# Main-board.net
KiCad netlist of a schematic drawn in EAGLE
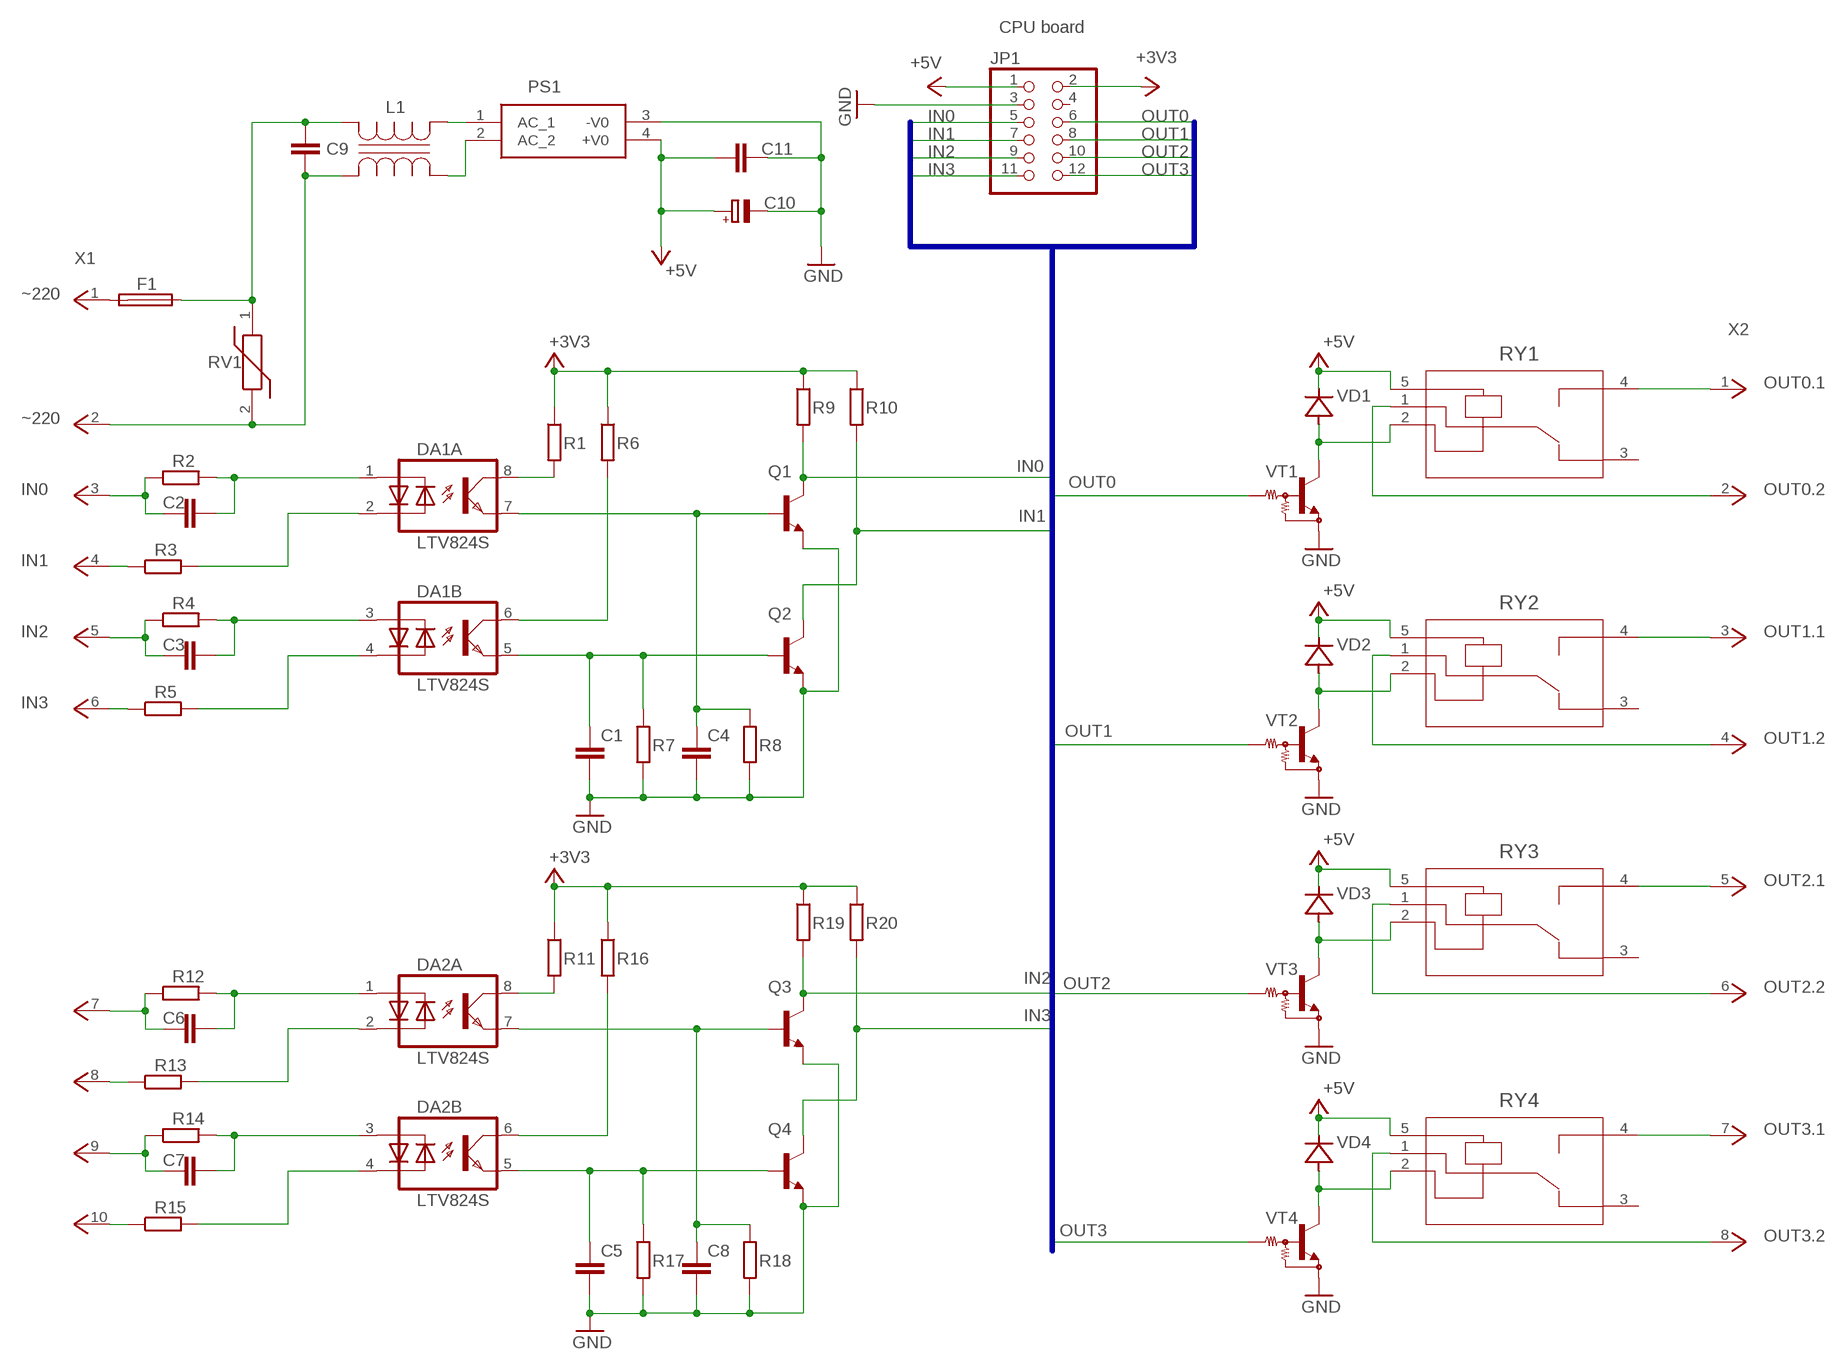
[diagram p0: schematic, sheet 1]

(export (version "E")
  (design (tool "Eeschema 10.0.6"))
  (components
    (comp (ref "C1")
      (value "0,1u")
      (footprint "eagle-import:C0603")
      (fields (field (name "VOLTAGE") "50V"))
      (libsource (lib "eagle-import") (part "C-EUC0603"))
    )
    (comp (ref "C2")
      (value "33n")
      (footprint "eagle-import:C1812")
      (fields (field (name "VOLTAGE") "500V"))
      (libsource (lib "eagle-import") (part "C-EUC1812"))
    )
    (comp (ref "C3")
      (value "33n")
      (footprint "eagle-import:C1812")
      (fields (field (name "VOLTAGE") "500V"))
      (libsource (lib "eagle-import") (part "C-EUC1812"))
    )
    (comp (ref "C4")
      (value "0,1u")
      (footprint "eagle-import:C0603")
      (fields (field (name "VOLTAGE") "50V"))
      (libsource (lib "eagle-import") (part "C-EUC0603"))
    )
    (comp (ref "C5")
      (value "0,1u")
      (footprint "eagle-import:C0603")
      (fields (field (name "VOLTAGE") "50V"))
      (libsource (lib "eagle-import") (part "C-EUC0603"))
    )
    (comp (ref "C6")
      (value "33n")
      (footprint "eagle-import:C1812")
      (fields (field (name "VOLTAGE") "500V"))
      (libsource (lib "eagle-import") (part "C-EUC1812"))
    )
    (comp (ref "C7")
      (value "33n")
      (footprint "eagle-import:C1812")
      (fields (field (name "VOLTAGE") "500V"))
      (libsource (lib "eagle-import") (part "C-EUC1812"))
    )
    (comp (ref "C8")
      (value "0,1u")
      (footprint "eagle-import:C0603")
      (fields (field (name "VOLTAGE") "50V"))
      (libsource (lib "eagle-import") (part "C-EUC0603"))
    )
    (comp (ref "C9")
      (value "R46KI310000M1K")
      (footprint "eagle-import:CAP_R46KI310000M1K")
      (fields (field (name "COPYRIGHT") "Copyright (C) 2018 Accelerated Designs. All rights reserved"))
      (libsource (lib "eagle-import") (part "R46KI310000M1K"))
    )
    (comp (ref "C10")
      (value "220uF")
      (footprint "eagle-import:D_7343-31W")
      (fields (field (name "TOLERANCE") "+/-10%") (field (name "VOLTAGE") "10V"))
      (libsource (lib "eagle-import") (part "CPOL-EUD/7343-31W"))
    )
    (comp (ref "C11")
      (value "0,1u")
      (footprint "eagle-import:C0603")
      (fields (field (name "VOLTAGE") "50V"))
      (libsource (lib "eagle-import") (part "C-EUC0603"))
    )
    (comp (ref "DA1")
      (value "LTV824S")
      (footprint "eagle-import:DIL8-SMD")
      (libsource (lib "eagle-import") (part "LTV824S"))
    )
    (comp (ref "DA2")
      (value "LTV824S")
      (footprint "eagle-import:DIL8-SMD")
      (libsource (lib "eagle-import") (part "LTV824S"))
    )
    (comp (ref "F1")
      (value "0,5A")
      (footprint "eagle-import:TR5")
      (libsource (lib "eagle-import") (part "TR5"))
    )
    (comp (ref "JP1")
      (value "NOT INSTALLED")
      (footprint "eagle-import:2X06")
      (libsource (lib "eagle-import") (part "PINHD-2X6"))
    )
    (comp (ref "L1")
      (value "DLW5BSN152SQ2L")
      (footprint "eagle-import:IND_DLW5BS_2020")
      (libsource (lib "eagle-import") (part "DLW5BSN152SQ2L"))
    )
    (comp (ref "PS1")
      (value "HLK-10M05")
      (footprint "eagle-import:HLK10M05")
      (libsource (lib "eagle-import") (part "HLK-10M05"))
    )
    (comp (ref "Q1")
      (value "BC847ALT1SMD")
      (footprint "eagle-import:SOT23")
      (libsource (lib "eagle-import") (part "BC847SMDALT1"))
    )
    (comp (ref "Q2")
      (value "BC847ALT1SMD")
      (footprint "eagle-import:SOT23")
      (libsource (lib "eagle-import") (part "BC847SMDALT1"))
    )
    (comp (ref "Q3")
      (value "BC847ALT1SMD")
      (footprint "eagle-import:SOT23")
      (libsource (lib "eagle-import") (part "BC847SMDALT1"))
    )
    (comp (ref "Q4")
      (value "BC847ALT1SMD")
      (footprint "eagle-import:SOT23")
      (libsource (lib "eagle-import") (part "BC847SMDALT1"))
    )
    (comp (ref "R1")
      (value "2,2k")
      (footprint "eagle-import:R0603")
      (fields (field (name "TOLERANCE") "1%"))
      (libsource (lib "eagle-import") (part "R-EU_R0603"))
    )
    (comp (ref "R2")
      (value "330k")
      (footprint "eagle-import:R2512")
      (fields (field (name "TOLERANCE") "5%"))
      (libsource (lib "eagle-import") (part "R-EU_R2512"))
    )
    (comp (ref "R3")
      (value "51")
      (footprint "eagle-import:R2512")
      (fields (field (name "TOLERANCE") "5%"))
      (libsource (lib "eagle-import") (part "R-EU_R2512"))
    )
    (comp (ref "R4")
      (value "330 k")
      (footprint "eagle-import:R2512")
      (fields (field (name "TOLERANCE") "5%"))
      (libsource (lib "eagle-import") (part "R-EU_R2512"))
    )
    (comp (ref "R5")
      (value "51")
      (footprint "eagle-import:R2512")
      (fields (field (name "TOLERANCE") "5%"))
      (libsource (lib "eagle-import") (part "R-EU_R2512"))
    )
    (comp (ref "R6")
      (value "2,2k")
      (footprint "eagle-import:R0603")
      (fields (field (name "TOLERANCE") "1%"))
      (libsource (lib "eagle-import") (part "R-EU_R0603"))
    )
    (comp (ref "R7")
      (value "33k")
      (footprint "eagle-import:R0603")
      (fields (field (name "TOLERANCE") "1%"))
      (libsource (lib "eagle-import") (part "R-EU_R0603"))
    )
    (comp (ref "R8")
      (value "33k")
      (footprint "eagle-import:R0603")
      (fields (field (name "TOLERANCE") "1%"))
      (libsource (lib "eagle-import") (part "R-EU_R0603"))
    )
    (comp (ref "R9")
      (value "10k")
      (footprint "eagle-import:R0603")
      (fields (field (name "TOLERANCE") "1%"))
      (libsource (lib "eagle-import") (part "R-EU_R0603"))
    )
    (comp (ref "R10")
      (value "10k")
      (footprint "eagle-import:R0603")
      (fields (field (name "TOLERANCE") "1%"))
      (libsource (lib "eagle-import") (part "R-EU_R0603"))
    )
    (comp (ref "R11")
      (value "2,2k")
      (footprint "eagle-import:R0603")
      (fields (field (name "TOLERANCE") "1%"))
      (libsource (lib "eagle-import") (part "R-EU_R0603"))
    )
    (comp (ref "R12")
      (value "330k")
      (footprint "eagle-import:R2512")
      (fields (field (name "TOLERANCE") "5%"))
      (libsource (lib "eagle-import") (part "R-EU_R2512"))
    )
    (comp (ref "R13")
      (value "51")
      (footprint "eagle-import:R2512")
      (fields (field (name "TOLERANCE") "5%"))
      (libsource (lib "eagle-import") (part "R-EU_R2512"))
    )
    (comp (ref "R14")
      (value "330 k")
      (footprint "eagle-import:R2512")
      (fields (field (name "TOLERANCE") "5%"))
      (libsource (lib "eagle-import") (part "R-EU_R2512"))
    )
    (comp (ref "R15")
      (value "51")
      (footprint "eagle-import:R2512")
      (fields (field (name "TOLERANCE") "5%"))
      (libsource (lib "eagle-import") (part "R-EU_R2512"))
    )
    (comp (ref "R16")
      (value "2,2k")
      (footprint "eagle-import:R0603")
      (fields (field (name "TOLERANCE") "1%"))
      (libsource (lib "eagle-import") (part "R-EU_R0603"))
    )
    (comp (ref "R17")
      (value "33k")
      (footprint "eagle-import:R0603")
      (fields (field (name "TOLERANCE") "1%"))
      (libsource (lib "eagle-import") (part "R-EU_R0603"))
    )
    (comp (ref "R18")
      (value "33k")
      (footprint "eagle-import:R0603")
      (fields (field (name "TOLERANCE") "1%"))
      (libsource (lib "eagle-import") (part "R-EU_R0603"))
    )
    (comp (ref "R19")
      (value "10k")
      (footprint "eagle-import:R0603")
      (fields (field (name "TOLERANCE") "1%"))
      (libsource (lib "eagle-import") (part "R-EU_R0603"))
    )
    (comp (ref "R20")
      (value "10k")
      (footprint "eagle-import:R0603")
      (fields (field (name "TOLERANCE") "1%"))
      (libsource (lib "eagle-import") (part "R-EU_R0603"))
    )
    (comp (ref "RV1")
      (value "VDR-10D561KJ")
      (footprint "eagle-import:VDR10D561KJ")
      (libsource (lib "eagle-import") (part "VDR-10D561KJ"))
    )
    (comp (ref "RY1")
      (value "SRD-05VDC-SL-C")
      (footprint "eagle-import:RELAY_SRD-05VDC-SL-C")
      (fields (field (name "COPYRIGHT") "Copyright (C) 2018 Accelerated Designs. All rights reserved"))
      (libsource (lib "eagle-import") (part "SRD-05VDC-SL-C"))
    )
    (comp (ref "RY2")
      (value "SRD-05VDC-SL-C")
      (footprint "eagle-import:RELAY_SRD-05VDC-SL-C")
      (fields (field (name "COPYRIGHT") "Copyright (C) 2018 Accelerated Designs. All rights reserved"))
      (libsource (lib "eagle-import") (part "SRD-05VDC-SL-C"))
    )
    (comp (ref "RY3")
      (value "SRD-05VDC-SL-C")
      (footprint "eagle-import:RELAY_SRD-05VDC-SL-C")
      (fields (field (name "COPYRIGHT") "Copyright (C) 2018 Accelerated Designs. All rights reserved"))
      (libsource (lib "eagle-import") (part "SRD-05VDC-SL-C"))
    )
    (comp (ref "RY4")
      (value "SRD-05VDC-SL-C")
      (footprint "eagle-import:RELAY_SRD-05VDC-SL-C")
      (fields (field (name "COPYRIGHT") "Copyright (C) 2018 Accelerated Designs. All rights reserved"))
      (libsource (lib "eagle-import") (part "SRD-05VDC-SL-C"))
    )
    (comp (ref "VD1")
      (value "LL4148")
      (footprint "eagle-import:SOD80C")
      (libsource (lib "eagle-import") (part "LL4148"))
    )
    (comp (ref "VD2")
      (value "LL4148")
      (footprint "eagle-import:SOD80C")
      (libsource (lib "eagle-import") (part "LL4148"))
    )
    (comp (ref "VD3")
      (value "LL4148")
      (footprint "eagle-import:SOD80C")
      (libsource (lib "eagle-import") (part "LL4148"))
    )
    (comp (ref "VD4")
      (value "LL4148")
      (footprint "eagle-import:SOD80C")
      (libsource (lib "eagle-import") (part "LL4148"))
    )
    (comp (ref "VT1")
      (value "BCR108E6327")
      (footprint "eagle-import:SOT23_1")
      (libsource (lib "eagle-import") (part "BCR108E6327"))
    )
    (comp (ref "VT2")
      (value "BCR108E6327")
      (footprint "eagle-import:SOT23_1")
      (libsource (lib "eagle-import") (part "BCR108E6327"))
    )
    (comp (ref "VT3")
      (value "BCR108E6327")
      (footprint "eagle-import:SOT23_1")
      (libsource (lib "eagle-import") (part "BCR108E6327"))
    )
    (comp (ref "VT4")
      (value "BCR108E6327")
      (footprint "eagle-import:SOT23_1")
      (libsource (lib "eagle-import") (part "BCR108E6327"))
    )
    (comp (ref "X1")
      (value "2EHDCR-5.08-10P")
      (footprint "eagle-import:2EHDCR-5.08-10P")
      (libsource (lib "eagle-import") (part "2EHDCR-5.08-10P"))
    )
    (comp (ref "X2")
      (value "2EHDCR-5.08-08P")
      (footprint "eagle-import:2EHDCR-5.08-08P")
      (libsource (lib "eagle-import") (part "2EHDCR-5.08-08P"))
    )
  )
  (nets
    (net (code "1") (name "+3V3") (class "Default")
      (node (ref "JP1") (pin "2") (pinfunction "2_2") (pintype "passive"))
      (node (ref "R1") (pin "1") (pinfunction "1_1") (pintype "passive"))
      (node (ref "R10") (pin "1") (pinfunction "1_1") (pintype "passive"))
      (node (ref "R11") (pin "1") (pinfunction "1_1") (pintype "passive"))
      (node (ref "R16") (pin "1") (pinfunction "1_1") (pintype "passive"))
      (node (ref "R19") (pin "1") (pinfunction "1_1") (pintype "passive"))
      (node (ref "R20") (pin "1") (pinfunction "1_1") (pintype "passive"))
      (node (ref "R6") (pin "1") (pinfunction "1_1") (pintype "passive"))
      (node (ref "R9") (pin "1") (pinfunction "1_1") (pintype "passive"))
    )
    (net (code "2") (name "+5V") (class "Default")
      (node (ref "C10") (pin "+") (pinfunction "+_+") (pintype "passive"))
      (node (ref "C11") (pin "1") (pinfunction "1_1") (pintype "passive"))
      (node (ref "JP1") (pin "1") (pinfunction "1_1") (pintype "passive"))
      (node (ref "PS1") (pin "4") (pinfunction "+V0_4") (pintype "bidirectional"))
      (node (ref "RY1") (pin "5") (pinfunction "5_5") (pintype "passive"))
      (node (ref "RY2") (pin "5") (pinfunction "5_5") (pintype "passive"))
      (node (ref "RY3") (pin "5") (pinfunction "5_5") (pintype "passive"))
      (node (ref "RY4") (pin "5") (pinfunction "5_5") (pintype "passive"))
      (node (ref "VD1") (pin "C") (pinfunction "C_C") (pintype "passive"))
      (node (ref "VD2") (pin "C") (pinfunction "C_C") (pintype "passive"))
      (node (ref "VD3") (pin "C") (pinfunction "C_C") (pintype "passive"))
      (node (ref "VD4") (pin "C") (pinfunction "C_C") (pintype "passive"))
    )
    (net (code "3") (name "/IN0") (class "Default")
      (node (ref "JP1") (pin "5") (pinfunction "5_5") (pintype "passive"))
      (node (ref "Q1") (pin "3") (pinfunction "C_3") (pintype "passive"))
      (node (ref "R9") (pin "2") (pinfunction "2_2") (pintype "passive"))
    )
    (net (code "4") (name "/IN1") (class "Default")
      (node (ref "JP1") (pin "7") (pinfunction "7_7") (pintype "passive"))
      (node (ref "Q2") (pin "3") (pinfunction "C_3") (pintype "passive"))
      (node (ref "R10") (pin "2") (pinfunction "2_2") (pintype "passive"))
    )
    (net (code "5") (name "/IN2") (class "Default")
      (node (ref "JP1") (pin "9") (pinfunction "9_9") (pintype "passive"))
      (node (ref "Q3") (pin "3") (pinfunction "C_3") (pintype "passive"))
      (node (ref "R19") (pin "2") (pinfunction "2_2") (pintype "passive"))
    )
    (net (code "6") (name "/IN3") (class "Default")
      (node (ref "JP1") (pin "11") (pinfunction "11_11") (pintype "passive"))
      (node (ref "Q4") (pin "3") (pinfunction "C_3") (pintype "passive"))
      (node (ref "R20") (pin "2") (pinfunction "2_2") (pintype "passive"))
    )
    (net (code "7") (name "/OUT0") (class "Default")
      (node (ref "JP1") (pin "6") (pinfunction "6_6") (pintype "passive"))
      (node (ref "VT1") (pin "1") (pinfunction "1_1") (pintype "passive"))
    )
    (net (code "8") (name "/OUT1") (class "Default")
      (node (ref "JP1") (pin "8") (pinfunction "8_8") (pintype "passive"))
      (node (ref "VT2") (pin "1") (pinfunction "1_1") (pintype "passive"))
    )
    (net (code "9") (name "/OUT2") (class "Default")
      (node (ref "JP1") (pin "10") (pinfunction "10_10") (pintype "passive"))
      (node (ref "VT3") (pin "1") (pinfunction "1_1") (pintype "passive"))
    )
    (net (code "10") (name "/OUT3") (class "Default")
      (node (ref "JP1") (pin "12") (pinfunction "12_12") (pintype "passive"))
      (node (ref "VT4") (pin "1") (pinfunction "1_1") (pintype "passive"))
    )
    (net (code "11") (name "GND") (class "Default")
      (node (ref "C1") (pin "2") (pinfunction "2_2") (pintype "passive"))
      (node (ref "C10") (pin "-") (pinfunction "-_-") (pintype "passive"))
      (node (ref "C11") (pin "2") (pinfunction "2_2") (pintype "passive"))
      (node (ref "C4") (pin "2") (pinfunction "2_2") (pintype "passive"))
      (node (ref "C5") (pin "2") (pinfunction "2_2") (pintype "passive"))
      (node (ref "C8") (pin "2") (pinfunction "2_2") (pintype "passive"))
      (node (ref "JP1") (pin "3") (pinfunction "3_3") (pintype "passive"))
      (node (ref "PS1") (pin "3") (pinfunction "-V0_3") (pintype "bidirectional"))
      (node (ref "Q1") (pin "2") (pinfunction "E_2") (pintype "passive"))
      (node (ref "Q2") (pin "2") (pinfunction "E_2") (pintype "passive"))
      (node (ref "Q3") (pin "2") (pinfunction "E_2") (pintype "passive"))
      (node (ref "Q4") (pin "2") (pinfunction "E_2") (pintype "passive"))
      (node (ref "R17") (pin "2") (pinfunction "2_2") (pintype "passive"))
      (node (ref "R18") (pin "2") (pinfunction "2_2") (pintype "passive"))
      (node (ref "R7") (pin "2") (pinfunction "2_2") (pintype "passive"))
      (node (ref "R8") (pin "2") (pinfunction "2_2") (pintype "passive"))
      (node (ref "VT1") (pin "2") (pinfunction "2_2") (pintype "passive"))
      (node (ref "VT2") (pin "2") (pinfunction "2_2") (pintype "passive"))
      (node (ref "VT3") (pin "2") (pinfunction "2_2") (pintype "passive"))
      (node (ref "VT4") (pin "2") (pinfunction "2_2") (pintype "passive"))
    )
    (net (code "12") (name "Net-(C9-Pad2)") (class "Default")
      (node (ref "C9") (pin "2") (pinfunction "2_2") (pintype "passive"))
      (node (ref "F1") (pin "1") (pinfunction "1_1") (pintype "passive"))
      (node (ref "L1") (pin "1") (pinfunction "1_1") (pintype "passive"))
      (node (ref "RV1") (pin "1") (pinfunction "1_1") (pintype "bidirectional"))
    )
    (net (code "13") (name "Net-(DA1A-A)") (class "Default")
      (node (ref "C2") (pin "2") (pinfunction "2_2") (pintype "passive"))
      (node (ref "DA1") (pin "1") (pinfunction "A_1") (pintype "passive"))
      (node (ref "R2") (pin "2") (pinfunction "2_2") (pintype "passive"))
    )
    (net (code "14") (name "Net-(DA1A-C)") (class "Default")
      (node (ref "DA1") (pin "2") (pinfunction "C_2") (pintype "passive"))
      (node (ref "R3") (pin "2") (pinfunction "2_2") (pintype "passive"))
    )
    (net (code "15") (name "Net-(DA1A-COL)") (class "Default")
      (node (ref "DA1") (pin "8") (pinfunction "COL_8") (pintype "passive"))
      (node (ref "R1") (pin "2") (pinfunction "2_2") (pintype "passive"))
    )
    (net (code "16") (name "Net-(DA1A-EMIT)") (class "Default")
      (node (ref "C4") (pin "1") (pinfunction "1_1") (pintype "passive"))
      (node (ref "DA1") (pin "7") (pinfunction "EMIT_7") (pintype "passive"))
      (node (ref "Q1") (pin "1") (pinfunction "B_1") (pintype "passive"))
      (node (ref "R8") (pin "1") (pinfunction "1_1") (pintype "passive"))
    )
    (net (code "17") (name "Net-(DA1B-A)") (class "Default")
      (node (ref "C3") (pin "2") (pinfunction "2_2") (pintype "passive"))
      (node (ref "DA1") (pin "3") (pinfunction "A_3") (pintype "passive"))
      (node (ref "R4") (pin "2") (pinfunction "2_2") (pintype "passive"))
    )
    (net (code "18") (name "Net-(DA1B-C)") (class "Default")
      (node (ref "DA1") (pin "4") (pinfunction "C_4") (pintype "passive"))
      (node (ref "R5") (pin "2") (pinfunction "2_2") (pintype "passive"))
    )
    (net (code "19") (name "Net-(DA1B-COL)") (class "Default")
      (node (ref "DA1") (pin "6") (pinfunction "COL_6") (pintype "passive"))
      (node (ref "R6") (pin "2") (pinfunction "2_2") (pintype "passive"))
    )
    (net (code "20") (name "Net-(DA1B-EMIT)") (class "Default")
      (node (ref "C1") (pin "1") (pinfunction "1_1") (pintype "passive"))
      (node (ref "DA1") (pin "5") (pinfunction "EMIT_5") (pintype "passive"))
      (node (ref "Q2") (pin "1") (pinfunction "B_1") (pintype "passive"))
      (node (ref "R7") (pin "1") (pinfunction "1_1") (pintype "passive"))
    )
    (net (code "21") (name "Net-(DA2A-A)") (class "Default")
      (node (ref "C6") (pin "2") (pinfunction "2_2") (pintype "passive"))
      (node (ref "DA2") (pin "1") (pinfunction "A_1") (pintype "passive"))
      (node (ref "R12") (pin "2") (pinfunction "2_2") (pintype "passive"))
    )
    (net (code "22") (name "Net-(DA2A-C)") (class "Default")
      (node (ref "DA2") (pin "2") (pinfunction "C_2") (pintype "passive"))
      (node (ref "R13") (pin "2") (pinfunction "2_2") (pintype "passive"))
    )
    (net (code "23") (name "Net-(DA2A-COL)") (class "Default")
      (node (ref "DA2") (pin "8") (pinfunction "COL_8") (pintype "passive"))
      (node (ref "R11") (pin "2") (pinfunction "2_2") (pintype "passive"))
    )
    (net (code "24") (name "Net-(DA2A-EMIT)") (class "Default")
      (node (ref "C8") (pin "1") (pinfunction "1_1") (pintype "passive"))
      (node (ref "DA2") (pin "7") (pinfunction "EMIT_7") (pintype "passive"))
      (node (ref "Q3") (pin "1") (pinfunction "B_1") (pintype "passive"))
      (node (ref "R18") (pin "1") (pinfunction "1_1") (pintype "passive"))
    )
    (net (code "25") (name "Net-(DA2B-A)") (class "Default")
      (node (ref "C7") (pin "2") (pinfunction "2_2") (pintype "passive"))
      (node (ref "DA2") (pin "3") (pinfunction "A_3") (pintype "passive"))
      (node (ref "R14") (pin "2") (pinfunction "2_2") (pintype "passive"))
    )
    (net (code "26") (name "Net-(DA2B-C)") (class "Default")
      (node (ref "DA2") (pin "4") (pinfunction "C_4") (pintype "passive"))
      (node (ref "R15") (pin "2") (pinfunction "2_2") (pintype "passive"))
    )
    (net (code "27") (name "Net-(DA2B-COL)") (class "Default")
      (node (ref "DA2") (pin "6") (pinfunction "COL_6") (pintype "passive"))
      (node (ref "R16") (pin "2") (pinfunction "2_2") (pintype "passive"))
    )
    (net (code "28") (name "Net-(DA2B-EMIT)") (class "Default")
      (node (ref "C5") (pin "1") (pinfunction "1_1") (pintype "passive"))
      (node (ref "DA2") (pin "5") (pinfunction "EMIT_5") (pintype "passive"))
      (node (ref "Q4") (pin "1") (pinfunction "B_1") (pintype "passive"))
      (node (ref "R17") (pin "1") (pinfunction "1_1") (pintype "passive"))
    )
    (net (code "29") (name "Net-(F1-Pad2)") (class "Default")
      (node (ref "F1") (pin "2") (pinfunction "2_2") (pintype "passive"))
      (node (ref "X1") (pin "1") (pinfunction "1_1") (pintype "passive"))
    )
    (net (code "30") (name "Net-(PS1-AC_1)") (class "Default")
      (node (ref "L1") (pin "2") (pinfunction "2_2") (pintype "passive"))
      (node (ref "PS1") (pin "1") (pinfunction "AC_1_1") (pintype "bidirectional"))
    )
    (net (code "31") (name "Net-(PS1-AC_2)") (class "Default")
      (node (ref "L1") (pin "3") (pinfunction "3_3") (pintype "passive"))
      (node (ref "PS1") (pin "2") (pinfunction "AC_2_2") (pintype "bidirectional"))
    )
    (net (code "32") (name "Net-(RY1-Pad2)") (class "Default")
      (node (ref "RY1") (pin "2") (pinfunction "2_2") (pintype "passive"))
      (node (ref "VD1") (pin "A") (pinfunction "A_A") (pintype "passive"))
      (node (ref "VT1") (pin "3") (pinfunction "3_3") (pintype "passive"))
    )
    (net (code "33") (name "Net-(RY1-Pad4)") (class "Default")
      (node (ref "RY1") (pin "4") (pinfunction "4_4") (pintype "passive"))
      (node (ref "X2") (pin "1") (pinfunction "1_1") (pintype "passive"))
    )
    (net (code "34") (name "Net-(RY2-Pad2)") (class "Default")
      (node (ref "RY2") (pin "2") (pinfunction "2_2") (pintype "passive"))
      (node (ref "VD2") (pin "A") (pinfunction "A_A") (pintype "passive"))
      (node (ref "VT2") (pin "3") (pinfunction "3_3") (pintype "passive"))
    )
    (net (code "35") (name "Net-(RY3-Pad2)") (class "Default")
      (node (ref "RY3") (pin "2") (pinfunction "2_2") (pintype "passive"))
      (node (ref "VD3") (pin "A") (pinfunction "A_A") (pintype "passive"))
      (node (ref "VT3") (pin "3") (pinfunction "3_3") (pintype "passive"))
    )
    (net (code "36") (name "Net-(RY4-Pad2)") (class "Default")
      (node (ref "RY4") (pin "2") (pinfunction "2_2") (pintype "passive"))
      (node (ref "VD4") (pin "A") (pinfunction "A_A") (pintype "passive"))
      (node (ref "VT4") (pin "3") (pinfunction "3_3") (pintype "passive"))
    )
    (net (code "37") (name "Net-(X1B-1)") (class "Default")
      (node (ref "R15") (pin "1") (pinfunction "1_1") (pintype "passive"))
      (node (ref "X1") (pin "10") (pinfunction "1_10") (pintype "passive"))
    )
    (net (code "38") (name "Net-(X1C-1)") (class "Default")
      (node (ref "C9") (pin "1") (pinfunction "1_1") (pintype "passive"))
      (node (ref "L1") (pin "4") (pinfunction "4_4") (pintype "passive"))
      (node (ref "RV1") (pin "2") (pinfunction "2_2") (pintype "bidirectional"))
      (node (ref "X1") (pin "2") (pinfunction "1_2") (pintype "passive"))
    )
    (net (code "39") (name "Net-(X1D-1)") (class "Default")
      (node (ref "C2") (pin "1") (pinfunction "1_1") (pintype "passive"))
      (node (ref "R2") (pin "1") (pinfunction "1_1") (pintype "passive"))
      (node (ref "X1") (pin "3") (pinfunction "1_3") (pintype "passive"))
    )
    (net (code "40") (name "Net-(X1E-1)") (class "Default")
      (node (ref "R3") (pin "1") (pinfunction "1_1") (pintype "passive"))
      (node (ref "X1") (pin "4") (pinfunction "1_4") (pintype "passive"))
    )
    (net (code "41") (name "Net-(X1F-1)") (class "Default")
      (node (ref "C3") (pin "1") (pinfunction "1_1") (pintype "passive"))
      (node (ref "R4") (pin "1") (pinfunction "1_1") (pintype "passive"))
      (node (ref "X1") (pin "5") (pinfunction "1_5") (pintype "passive"))
    )
    (net (code "42") (name "Net-(X1G-1)") (class "Default")
      (node (ref "R5") (pin "1") (pinfunction "1_1") (pintype "passive"))
      (node (ref "X1") (pin "6") (pinfunction "1_6") (pintype "passive"))
    )
    (net (code "43") (name "Net-(X1H-1)") (class "Default")
      (node (ref "C6") (pin "1") (pinfunction "1_1") (pintype "passive"))
      (node (ref "R12") (pin "1") (pinfunction "1_1") (pintype "passive"))
      (node (ref "X1") (pin "7") (pinfunction "1_7") (pintype "passive"))
    )
    (net (code "44") (name "Net-(X1I-1)") (class "Default")
      (node (ref "R13") (pin "1") (pinfunction "1_1") (pintype "passive"))
      (node (ref "X1") (pin "8") (pinfunction "1_8") (pintype "passive"))
    )
    (net (code "45") (name "Net-(X1J-1)") (class "Default")
      (node (ref "C7") (pin "1") (pinfunction "1_1") (pintype "passive"))
      (node (ref "R14") (pin "1") (pinfunction "1_1") (pintype "passive"))
      (node (ref "X1") (pin "9") (pinfunction "1_9") (pintype "passive"))
    )
    (net (code "46") (name "Net-(X2B-1)") (class "Default")
      (node (ref "RY1") (pin "1") (pinfunction "1_1") (pintype "passive"))
      (node (ref "X2") (pin "2") (pinfunction "1_2") (pintype "passive"))
    )
    (net (code "47") (name "Net-(X2C-1)") (class "Default")
      (node (ref "RY2") (pin "4") (pinfunction "4_4") (pintype "passive"))
      (node (ref "X2") (pin "3") (pinfunction "1_3") (pintype "passive"))
    )
    (net (code "48") (name "Net-(X2D-1)") (class "Default")
      (node (ref "RY2") (pin "1") (pinfunction "1_1") (pintype "passive"))
      (node (ref "X2") (pin "4") (pinfunction "1_4") (pintype "passive"))
    )
    (net (code "49") (name "Net-(X2E-1)") (class "Default")
      (node (ref "RY3") (pin "4") (pinfunction "4_4") (pintype "passive"))
      (node (ref "X2") (pin "5") (pinfunction "1_5") (pintype "passive"))
    )
    (net (code "50") (name "Net-(X2F-1)") (class "Default")
      (node (ref "RY3") (pin "1") (pinfunction "1_1") (pintype "passive"))
      (node (ref "X2") (pin "6") (pinfunction "1_6") (pintype "passive"))
    )
    (net (code "51") (name "Net-(X2G-1)") (class "Default")
      (node (ref "RY4") (pin "4") (pinfunction "4_4") (pintype "passive"))
      (node (ref "X2") (pin "7") (pinfunction "1_7") (pintype "passive"))
    )
    (net (code "52") (name "Net-(X2H-1)") (class "Default")
      (node (ref "RY4") (pin "1") (pinfunction "1_1") (pintype "passive"))
      (node (ref "X2") (pin "8") (pinfunction "1_8") (pintype "passive"))
    )
    (net (code "53") (name "unconnected-(JP1-Pad4)") (class "Default")
      (node (ref "JP1") (pin "4") (pinfunction "4_4") (pintype "passive"))
    )
    (net (code "54") (name "unconnected-(RY1-Pad3)") (class "Default")
      (node (ref "RY1") (pin "3") (pinfunction "3_3") (pintype "passive"))
    )
    (net (code "55") (name "unconnected-(RY2-Pad3)") (class "Default")
      (node (ref "RY2") (pin "3") (pinfunction "3_3") (pintype "passive"))
    )
    (net (code "56") (name "unconnected-(RY3-Pad3)") (class "Default")
      (node (ref "RY3") (pin "3") (pinfunction "3_3") (pintype "passive"))
    )
    (net (code "57") (name "unconnected-(RY4-Pad3)") (class "Default")
      (node (ref "RY4") (pin "3") (pinfunction "3_3") (pintype "passive"))
    )
  )
)
